# SOT-143_to_breadboard.net
KiCad netlist of a schematic drawn in EAGLE
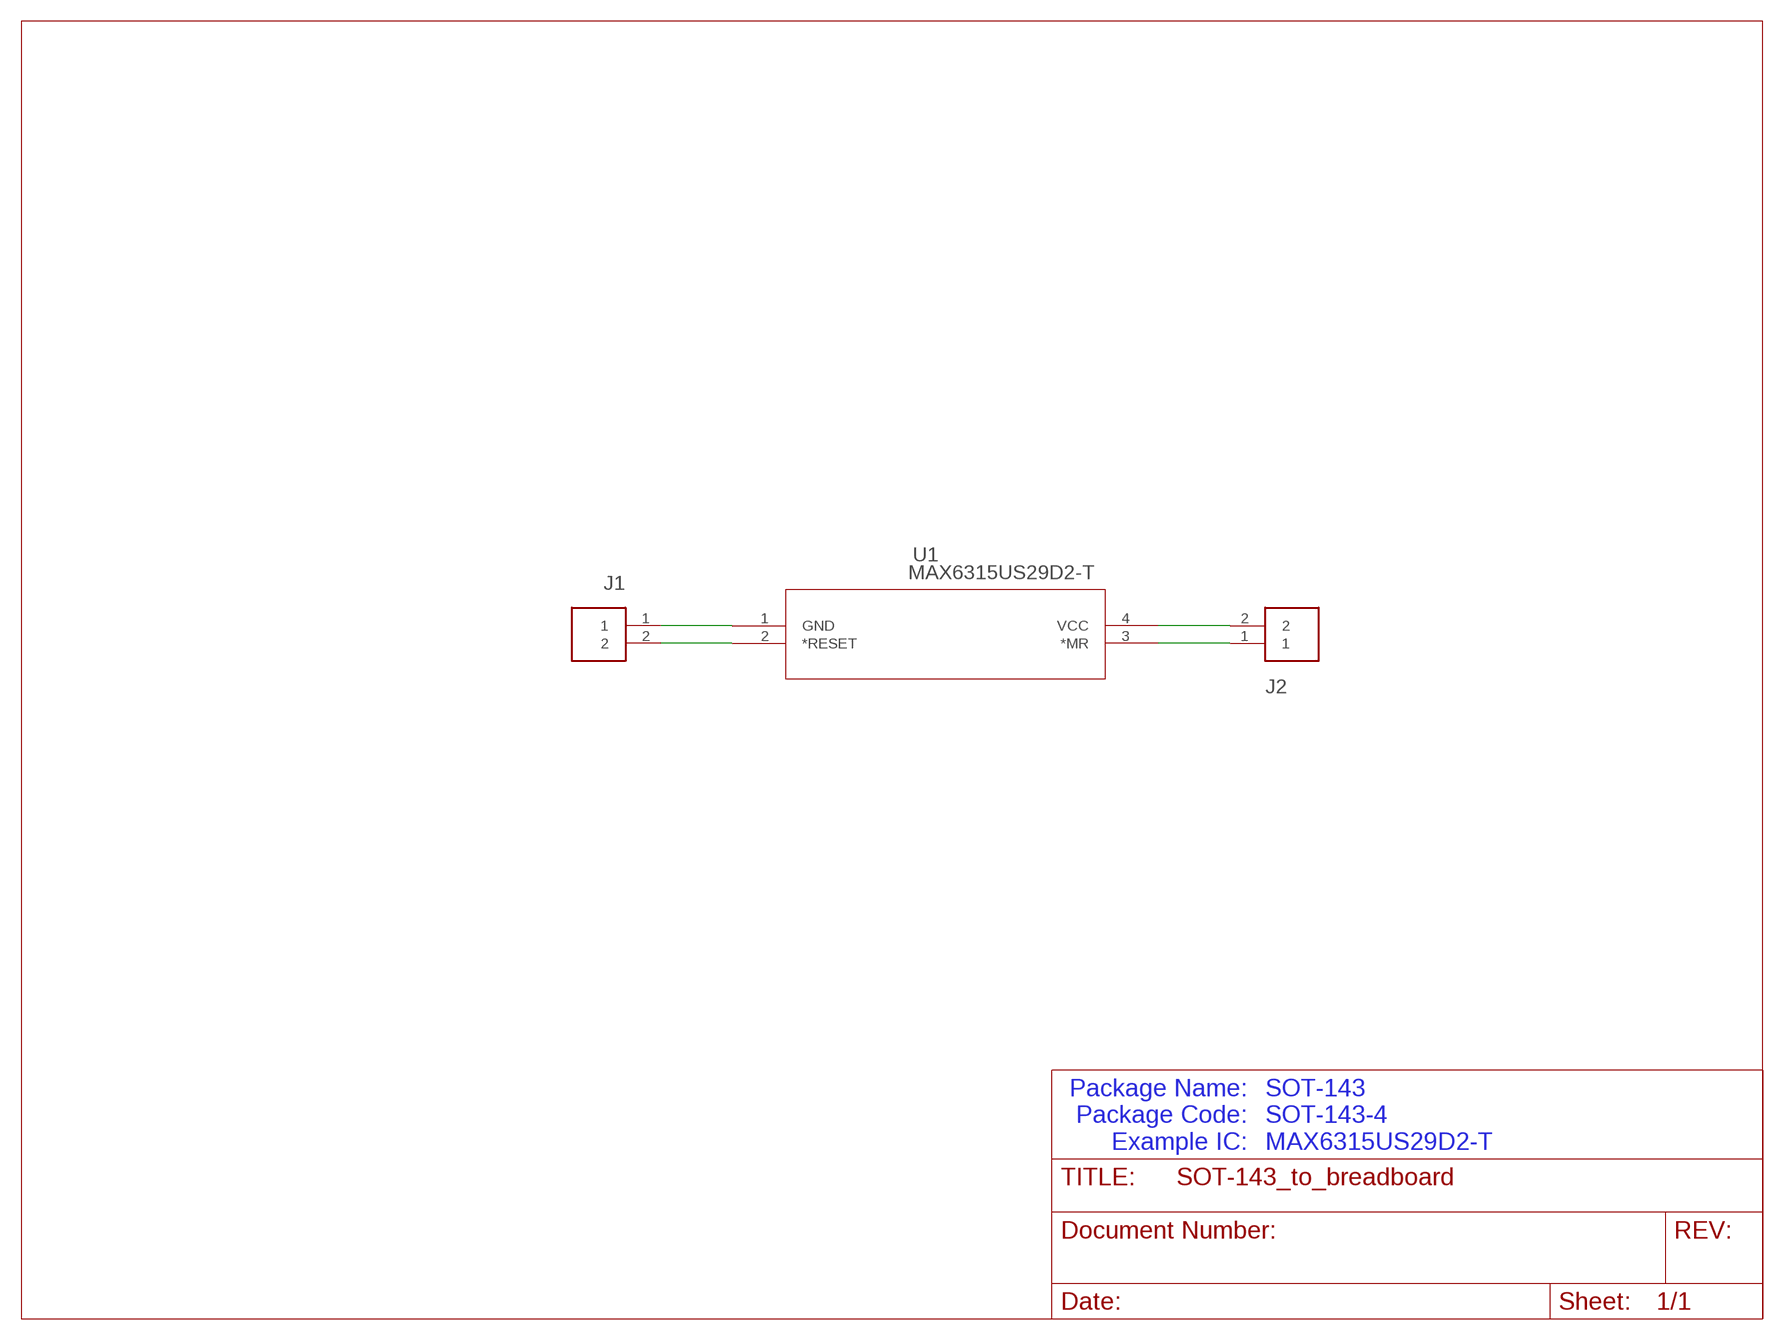
[diagram p0: schematic, sheet 1]

(export (version "E")
  (design (tool "Eeschema 10.0.6"))
  (components
    (comp (ref "J1")
      (value "CONNECTOR_2")
      (footprint "eagle-import:68000-102HLF")
      (libsource (lib "eagle-import") (part "CONNECTOR_2"))
    )
    (comp (ref "J2")
      (value "CONNECTOR_2-NO_SQUARE")
      (footprint "eagle-import:68000-102HLF_NO_SQUARE")
      (libsource (lib "eagle-import") (part "CONNECTOR_2-NO_SQUARE"))
    )
    (comp (ref "U1")
      (value "MAX6315US29D2-T")
      (footprint "eagle-import:21-0052F")
      (fields (field (name "MF") "Maxim Integrated") (field (name "MP") "MAX6315US29D2+T"))
      (libsource (lib "eagle-import") (part "MAX6315US29D2-T"))
    )
  )
  (nets
    (net (code "1") (name "Net-(U1-*MR)") (class "Default")
      (node (ref "J2") (pin "1") (pinfunction "1_1") (pintype "bidirectional"))
      (node (ref "U1") (pin "3") (pinfunction "*MR_3") (pintype "input"))
    )
    (net (code "2") (name "Net-(U1-*RESET)") (class "Default")
      (node (ref "J1") (pin "2") (pinfunction "2_2") (pintype "bidirectional"))
      (node (ref "U1") (pin "2") (pinfunction "*RESET_2") (pintype "output"))
    )
    (net (code "3") (name "Net-(U1-GND)") (class "Default")
      (node (ref "J1") (pin "1") (pinfunction "1_1") (pintype "bidirectional"))
      (node (ref "U1") (pin "1") (pinfunction "GND_1") (pintype "power_in"))
    )
    (net (code "4") (name "Net-(U1-VCC)") (class "Default")
      (node (ref "J2") (pin "2") (pinfunction "2_2") (pintype "bidirectional"))
      (node (ref "U1") (pin "4") (pinfunction "VCC_4") (pintype "power_in"))
    )
  )
)
